# GB_SOP32_ROM_Adapter_mini_version.net
KiCad netlist of a schematic drawn in EAGLE
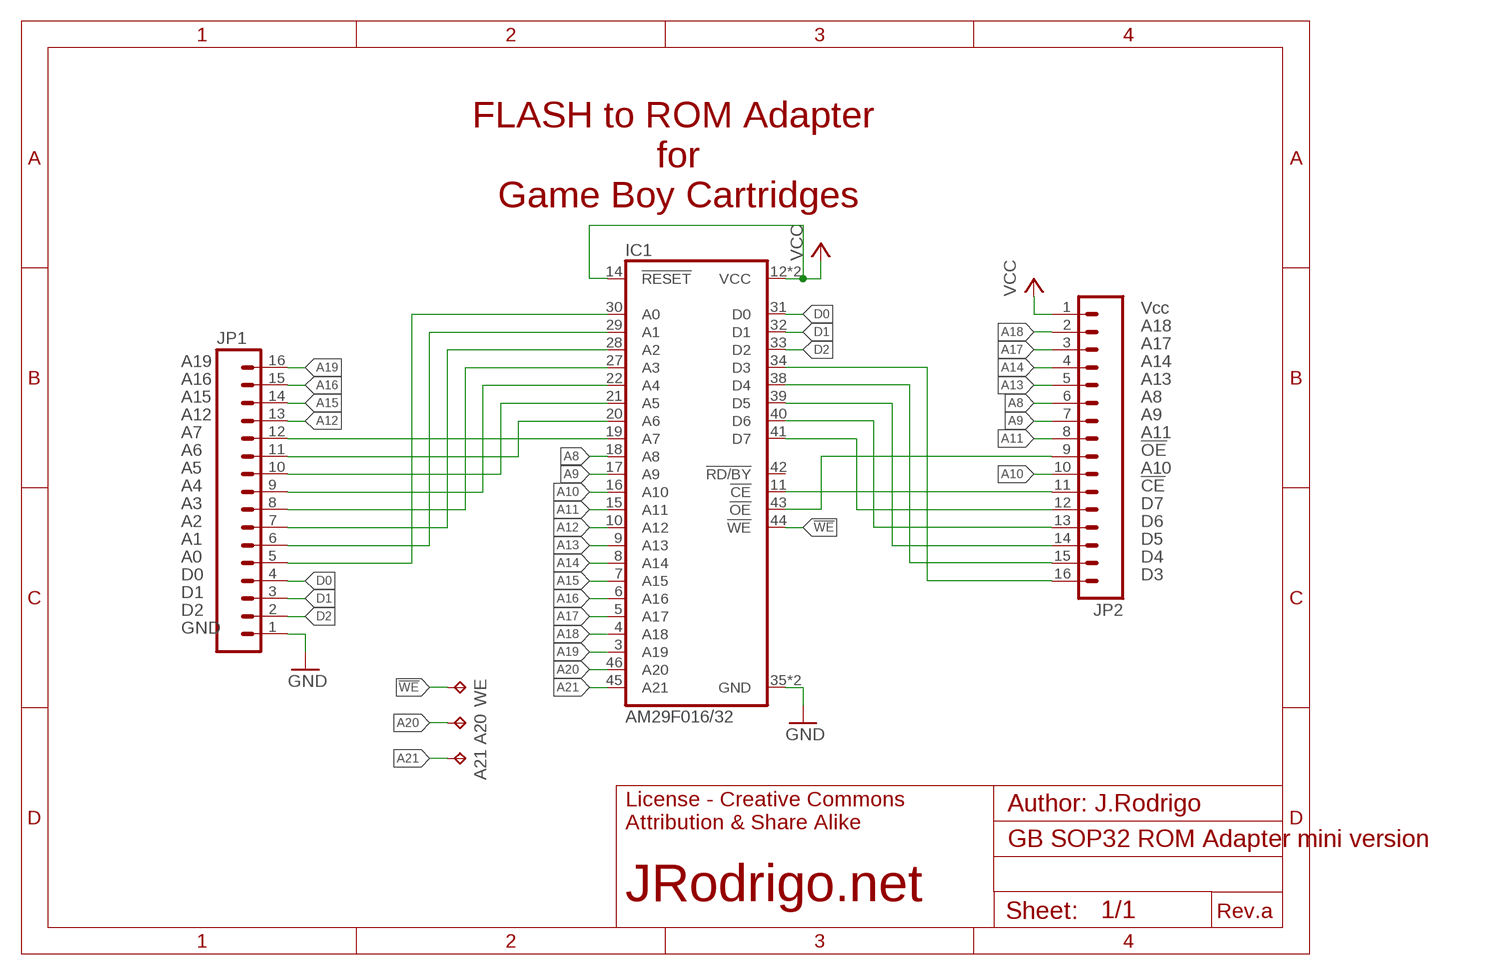
[diagram p0: schematic, sheet 1]

(export (version "E")
  (design (tool "Eeschema 10.0.6"))
  (components
    (comp (ref "A20")
      (value "TPTP06SQ")
      (footprint "eagle-import:TP06SQ")
      (libsource (lib "eagle-import") (part "TPTP06SQ"))
    )
    (comp (ref "A21")
      (value "TPTP06SQ")
      (footprint "eagle-import:TP06SQ")
      (libsource (lib "eagle-import") (part "TPTP06SQ"))
    )
    (comp (ref "IC1")
      (value "AM29F016/32")
      (footprint "eagle-import:TSOP48_WITHOUT_NC")
      (libsource (lib "eagle-import") (part "AM29FXXXTSOP48_WITHOUT_NC"))
    )
    (comp (ref "JP1")
      (value "CASTELLATIONS_16-PINS*")
      (footprint "eagle-import:CASTELLATIONS_16-PINS")
      (libsource (lib "eagle-import") (part "CASTELLATIONS_16-PINS"))
    )
    (comp (ref "JP2")
      (value "CASTELLATIONS_16-PINS*")
      (footprint "eagle-import:CASTELLATIONS_16-PINS")
      (libsource (lib "eagle-import") (part "CASTELLATIONS_16-PINS"))
    )
    (comp (ref "WE")
      (value "TPTP06SQ")
      (footprint "eagle-import:TP06SQ")
      (libsource (lib "eagle-import") (part "TPTP06SQ"))
    )
  )
  (nets
    (net (code "1") (name "/~{WE}") (class "Default")
      (node (ref "IC1") (pin "44") (pinfunction "~{WE}_44") (pintype "input"))
      (node (ref "WE") (pin "TP") (pinfunction "TP_TP") (pintype "input"))
    )
    (net (code "2") (name "A8") (class "Default")
      (node (ref "IC1") (pin "18") (pinfunction "A8_18") (pintype "input"))
      (node (ref "JP2") (pin "6") (pinfunction "6_6") (pintype "passive"))
    )
    (net (code "3") (name "A9") (class "Default")
      (node (ref "IC1") (pin "17") (pinfunction "A9_17") (pintype "input"))
      (node (ref "JP2") (pin "7") (pinfunction "7_7") (pintype "passive"))
    )
    (net (code "4") (name "A10") (class "Default")
      (node (ref "IC1") (pin "16") (pinfunction "A10_16") (pintype "input"))
      (node (ref "JP2") (pin "10") (pinfunction "10_10") (pintype "passive"))
    )
    (net (code "5") (name "A11") (class "Default")
      (node (ref "IC1") (pin "15") (pinfunction "A11_15") (pintype "input"))
      (node (ref "JP2") (pin "8") (pinfunction "8_8") (pintype "passive"))
    )
    (net (code "6") (name "A12") (class "Default")
      (node (ref "IC1") (pin "10") (pinfunction "A12_10") (pintype "input"))
      (node (ref "JP1") (pin "13") (pinfunction "13_13") (pintype "passive"))
    )
    (net (code "7") (name "A13") (class "Default")
      (node (ref "IC1") (pin "9") (pinfunction "A13_9") (pintype "input"))
      (node (ref "JP2") (pin "5") (pinfunction "5_5") (pintype "passive"))
    )
    (net (code "8") (name "A14") (class "Default")
      (node (ref "IC1") (pin "8") (pinfunction "A14_8") (pintype "input"))
      (node (ref "JP2") (pin "4") (pinfunction "4_4") (pintype "passive"))
    )
    (net (code "9") (name "A15") (class "Default")
      (node (ref "IC1") (pin "7") (pinfunction "A15_7") (pintype "input"))
      (node (ref "JP1") (pin "14") (pinfunction "14_14") (pintype "passive"))
    )
    (net (code "10") (name "A16") (class "Default")
      (node (ref "IC1") (pin "6") (pinfunction "A16_6") (pintype "input"))
      (node (ref "JP1") (pin "15") (pinfunction "15_15") (pintype "passive"))
    )
    (net (code "11") (name "A17") (class "Default")
      (node (ref "IC1") (pin "5") (pinfunction "A17_5") (pintype "input"))
      (node (ref "JP2") (pin "3") (pinfunction "3_3") (pintype "passive"))
    )
    (net (code "12") (name "A18") (class "Default")
      (node (ref "IC1") (pin "4") (pinfunction "A18_4") (pintype "input"))
      (node (ref "JP2") (pin "2") (pinfunction "2_2") (pintype "passive"))
    )
    (net (code "13") (name "A19") (class "Default")
      (node (ref "IC1") (pin "3") (pinfunction "A19_3") (pintype "input"))
      (node (ref "JP1") (pin "16") (pinfunction "16_16") (pintype "passive"))
    )
    (net (code "14") (name "A20") (class "Default")
      (node (ref "A20") (pin "TP") (pinfunction "TP_TP") (pintype "input"))
      (node (ref "IC1") (pin "46") (pinfunction "A20_46") (pintype "input"))
    )
    (net (code "15") (name "A21") (class "Default")
      (node (ref "A21") (pin "TP") (pinfunction "TP_TP") (pintype "input"))
      (node (ref "IC1") (pin "45") (pinfunction "A21_45") (pintype "input"))
    )
    (net (code "16") (name "D0") (class "Default")
      (node (ref "IC1") (pin "31") (pinfunction "D0_31") (pintype "tri_state"))
      (node (ref "JP1") (pin "4") (pinfunction "4_4") (pintype "passive"))
    )
    (net (code "17") (name "D1") (class "Default")
      (node (ref "IC1") (pin "32") (pinfunction "D1_32") (pintype "tri_state"))
      (node (ref "JP1") (pin "3") (pinfunction "3_3") (pintype "passive"))
    )
    (net (code "18") (name "D2") (class "Default")
      (node (ref "IC1") (pin "33") (pinfunction "D2_33") (pintype "tri_state"))
      (node (ref "JP1") (pin "2") (pinfunction "2_2") (pintype "passive"))
    )
    (net (code "19") (name "GND") (class "Default")
      (node (ref "IC1") (pin "35") (pinfunction "GND_35") (pintype "power_in"))
      (node (ref "IC1") (pin "36") (pinfunction "GND_36") (pintype "power_in"))
      (node (ref "JP1") (pin "1") (pinfunction "1_1") (pintype "passive"))
    )
    (net (code "20") (name "Net-(IC1-A0)") (class "Default")
      (node (ref "IC1") (pin "30") (pinfunction "A0_30") (pintype "input"))
      (node (ref "JP1") (pin "5") (pinfunction "5_5") (pintype "passive"))
    )
    (net (code "21") (name "Net-(IC1-A1)") (class "Default")
      (node (ref "IC1") (pin "29") (pinfunction "A1_29") (pintype "input"))
      (node (ref "JP1") (pin "6") (pinfunction "6_6") (pintype "passive"))
    )
    (net (code "22") (name "Net-(IC1-A2)") (class "Default")
      (node (ref "IC1") (pin "28") (pinfunction "A2_28") (pintype "input"))
      (node (ref "JP1") (pin "7") (pinfunction "7_7") (pintype "passive"))
    )
    (net (code "23") (name "Net-(IC1-A3)") (class "Default")
      (node (ref "IC1") (pin "27") (pinfunction "A3_27") (pintype "input"))
      (node (ref "JP1") (pin "8") (pinfunction "8_8") (pintype "passive"))
    )
    (net (code "24") (name "Net-(IC1-A4)") (class "Default")
      (node (ref "IC1") (pin "22") (pinfunction "A4_22") (pintype "input"))
      (node (ref "JP1") (pin "9") (pinfunction "9_9") (pintype "passive"))
    )
    (net (code "25") (name "Net-(IC1-A5)") (class "Default")
      (node (ref "IC1") (pin "21") (pinfunction "A5_21") (pintype "input"))
      (node (ref "JP1") (pin "10") (pinfunction "10_10") (pintype "passive"))
    )
    (net (code "26") (name "Net-(IC1-A6)") (class "Default")
      (node (ref "IC1") (pin "20") (pinfunction "A6_20") (pintype "input"))
      (node (ref "JP1") (pin "11") (pinfunction "11_11") (pintype "passive"))
    )
    (net (code "27") (name "Net-(IC1-A7)") (class "Default")
      (node (ref "IC1") (pin "19") (pinfunction "A7_19") (pintype "input"))
      (node (ref "JP1") (pin "12") (pinfunction "12_12") (pintype "passive"))
    )
    (net (code "28") (name "Net-(IC1-D3)") (class "Default")
      (node (ref "IC1") (pin "34") (pinfunction "D3_34") (pintype "tri_state"))
      (node (ref "JP2") (pin "16") (pinfunction "16_16") (pintype "passive"))
    )
    (net (code "29") (name "Net-(IC1-D4)") (class "Default")
      (node (ref "IC1") (pin "38") (pinfunction "D4_38") (pintype "tri_state"))
      (node (ref "JP2") (pin "15") (pinfunction "15_15") (pintype "passive"))
    )
    (net (code "30") (name "Net-(IC1-D5)") (class "Default")
      (node (ref "IC1") (pin "39") (pinfunction "D5_39") (pintype "tri_state"))
      (node (ref "JP2") (pin "14") (pinfunction "14_14") (pintype "passive"))
    )
    (net (code "31") (name "Net-(IC1-D6)") (class "Default")
      (node (ref "IC1") (pin "40") (pinfunction "D6_40") (pintype "tri_state"))
      (node (ref "JP2") (pin "13") (pinfunction "13_13") (pintype "passive"))
    )
    (net (code "32") (name "Net-(IC1-D7)") (class "Default")
      (node (ref "IC1") (pin "41") (pinfunction "D7_41") (pintype "tri_state"))
      (node (ref "JP2") (pin "12") (pinfunction "12_12") (pintype "passive"))
    )
    (net (code "33") (name "Net-(IC1-~{CE})") (class "Default")
      (node (ref "IC1") (pin "11") (pinfunction "~{CE}_11") (pintype "input"))
      (node (ref "JP2") (pin "11") (pinfunction "11_11") (pintype "passive"))
    )
    (net (code "34") (name "Net-(IC1-~{OE})") (class "Default")
      (node (ref "IC1") (pin "43") (pinfunction "~{OE}_43") (pintype "input"))
      (node (ref "JP2") (pin "9") (pinfunction "9_9") (pintype "passive"))
    )
    (net (code "35") (name "VCC") (class "Default")
      (node (ref "IC1") (pin "12") (pinfunction "VCC_12") (pintype "power_in"))
      (node (ref "IC1") (pin "14") (pinfunction "~{RESET}_14") (pintype "input"))
      (node (ref "IC1") (pin "37") (pinfunction "VCC_37") (pintype "power_in"))
      (node (ref "JP2") (pin "1") (pinfunction "1_1") (pintype "passive"))
    )
    (net (code "36") (name "unconnected-(IC1-~{RD{slash}BY}-Pad42)") (class "Default")
      (node (ref "IC1") (pin "42") (pinfunction "~{RD/BY}_42") (pintype "output"))
    )
  )
)
